# led_1_Arduino.net
KiCad netlist of a schematic drawn in EAGLE
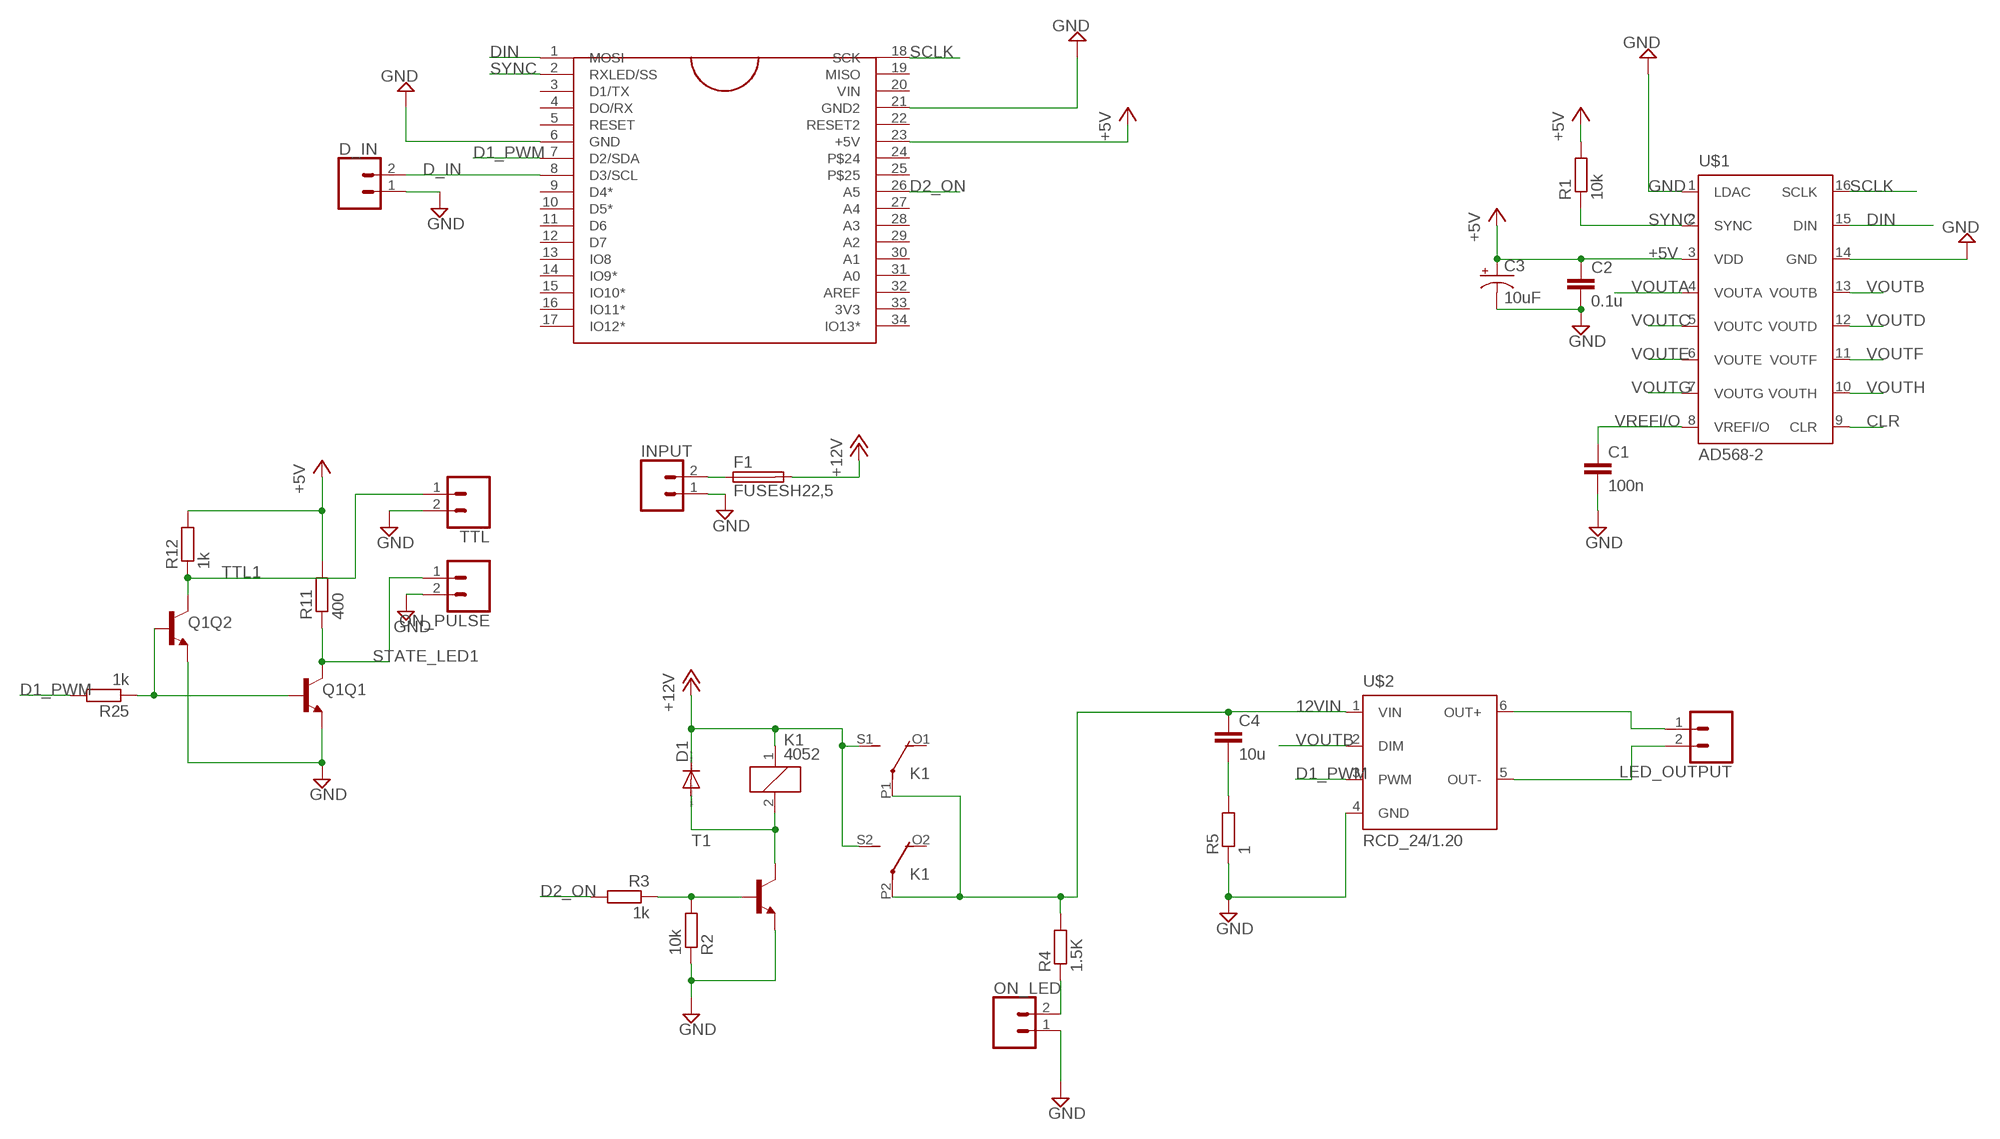
[diagram p0: schematic, sheet 1]

(export (version "E")
  (design (tool "Eeschema 10.0.6"))
  (components
    (comp (ref "C1")
      (value "100n")
      (footprint "eagle-import:C1206")
      (libsource (lib "eagle-import") (part "C-EUC1206"))
    )
    (comp (ref "C2")
      (value "0.1u")
      (footprint "eagle-import:C1206")
      (libsource (lib "eagle-import") (part "C-EUC1206"))
    )
    (comp (ref "C3")
      (value "10uF")
      (footprint "eagle-import:EIA3528")
      (libsource (lib "eagle-import") (part "10UF-POLAR-EIA3528-20V-10%(TANT)"))
    )
    (comp (ref "C4")
      (value "10u")
      (footprint "eagle-import:C1206")
      (libsource (lib "eagle-import") (part "C-EUC1206"))
    )
    (comp (ref "D1")
      (value "DIODE-DO214AC")
      (footprint "eagle-import:DO214AC")
      (libsource (lib "eagle-import") (part "DIODE-DO214AC"))
    )
    (comp (ref "D_IN")
      (value "CONN_02")
      (footprint "eagle-import:1X02")
      (libsource (lib "eagle-import") (part "CONN_02"))
    )
    (comp (ref "F1")
      (value "FUSESH22,5")
      (footprint "eagle-import:SH22,5")
      (libsource (lib "eagle-import") (part "FUSESH22,5"))
    )
    (comp (ref "INPUT")
      (value "CONN_023.5MM")
      (footprint "eagle-import:SCREWTERMINAL-3.5MM-2")
      (libsource (lib "eagle-import") (part "CONN_023.5MM"))
    )
    (comp (ref "K1")
      (value "4052")
      (footprint "eagle-import:F4052")
      (libsource (lib "eagle-import") (part "4052"))
    )
    (comp (ref "LED_OUTPUT")
      (value "CONN_023.5MM")
      (footprint "eagle-import:SCREWTERMINAL-3.5MM-2")
      (libsource (lib "eagle-import") (part "CONN_023.5MM"))
    )
    (comp (ref "ON_LED")
      (value "CONN_02")
      (footprint "eagle-import:1X02")
      (libsource (lib "eagle-import") (part "CONN_02"))
    )
    (comp (ref "ON_PULSE")
      (value "CONN_02")
      (footprint "eagle-import:1X02")
      (libsource (lib "eagle-import") (part "CONN_02"))
    )
    (comp (ref "Q1")
      (value "TRANS_NPN_DUAL_NSM4002-MBT3904DW1T1")
      (footprint "eagle-import:SC70-6")
      (libsource (lib "eagle-import") (part "TRANS_NPN_DUAL_NSM4002-MBT3904DW1T1"))
    )
    (comp (ref "R1")
      (value "10k")
      (footprint "eagle-import:R1206")
      (libsource (lib "eagle-import") (part "R-EU_R1206"))
    )
    (comp (ref "R2")
      (value "10k")
      (footprint "eagle-import:R1206")
      (libsource (lib "eagle-import") (part "R-EU_R1206"))
    )
    (comp (ref "R3")
      (value "1k")
      (footprint "eagle-import:R0805")
      (libsource (lib "eagle-import") (part "R-EU_R0805"))
    )
    (comp (ref "R4")
      (value "1.5K")
      (footprint "eagle-import:R0805")
      (libsource (lib "eagle-import") (part "R-EU_R0805"))
    )
    (comp (ref "R5")
      (value "1")
      (footprint "eagle-import:R1206")
      (libsource (lib "eagle-import") (part "R-EU_R1206"))
    )
    (comp (ref "R11")
      (value "400")
      (footprint "eagle-import:R0805")
      (libsource (lib "eagle-import") (part "R-EU_R0805"))
    )
    (comp (ref "R12")
      (value "1k")
      (footprint "eagle-import:R0805")
      (libsource (lib "eagle-import") (part "R-EU_R0805"))
    )
    (comp (ref "R25")
      (value "1k")
      (footprint "eagle-import:R0805")
      (libsource (lib "eagle-import") (part "R-EU_R0805"))
    )
    (comp (ref "T1")
      (value "-NPN-SOT223")
      (footprint "eagle-import:SOT223")
      (libsource (lib "eagle-import") (part "-NPN-SOT223"))
    )
    (comp (ref "TTL")
      (value "CONN_02")
      (footprint "eagle-import:1X02")
      (libsource (lib "eagle-import") (part "CONN_02"))
    )
    (comp (ref "U$1")
      (value "AD568-2")
      (footprint "eagle-import:TSSOP-16")
      (libsource (lib "eagle-import") (part "AD568-2"))
    )
    (comp (ref "U$2")
      (value "RCD_24/1.20")
      (footprint "eagle-import:RCD-24_W_X3")
      (libsource (lib "eagle-import") (part "RCD_24/1.20"))
    )
    (comp (ref "U$3")
      (value "ARDUINO_MICRO")
      (footprint "eagle-import:ARDUINO_MICRO_PADS")
      (fields (field (name "SPICEPREFIX") "X"))
      (libsource (lib "eagle-import") (part "ARDUINO_MICRO"))
    )
  )
  (nets
    (net (code "1") (name "+5V") (class "Default")
      (node (ref "C2") (pin "1") (pinfunction "1_1") (pintype "passive"))
      (node (ref "C3") (pin "A") (pinfunction "+_A") (pintype "passive"))
      (node (ref "R1") (pin "2") (pinfunction "2_2") (pintype "passive"))
      (node (ref "R11") (pin "2") (pinfunction "2_2") (pintype "passive"))
      (node (ref "R12") (pin "2") (pinfunction "2_2") (pintype "passive"))
      (node (ref "U$1") (pin "3") (pinfunction "VDD_3") (pintype "power_in"))
      (node (ref "U$3") (pin "23") (pinfunction "+5V_23") (pintype "bidirectional"))
    )
    (net (code "2") (name "+12V") (class "Default")
      (node (ref "D1") (pin "C") (pinfunction "C_C") (pintype "passive"))
      (node (ref "F1") (pin "2") (pinfunction "2_2") (pintype "passive"))
      (node (ref "K1") (pin "1") (pinfunction "1_1") (pintype "passive"))
      (node (ref "K1") (pin "S1") (pinfunction "S_S1") (pintype "passive"))
      (node (ref "K1") (pin "S2") (pinfunction "S_S2") (pintype "passive"))
    )
    (net (code "3") (name "/12VIN") (class "Default")
      (node (ref "C4") (pin "1") (pinfunction "1_1") (pintype "passive"))
      (node (ref "K1") (pin "P1") (pinfunction "P_P1") (pintype "passive"))
      (node (ref "K1") (pin "P2") (pinfunction "P_P2") (pintype "passive"))
      (node (ref "R4") (pin "2") (pinfunction "2_2") (pintype "passive"))
      (node (ref "U$2") (pin "1") (pinfunction "VIN_1") (pintype "input"))
    )
    (net (code "4") (name "/CLR") (class "Default")
      (node (ref "U$1") (pin "9") (pinfunction "CLR_9") (pintype "output"))
    )
    (net (code "5") (name "/D1_PWM") (class "Default")
      (node (ref "R25") (pin "2") (pinfunction "2_2") (pintype "passive"))
      (node (ref "U$2") (pin "3") (pinfunction "PWM_3") (pintype "passive"))
      (node (ref "U$3") (pin "7") (pinfunction "D2/SDA_7") (pintype "bidirectional"))
    )
    (net (code "6") (name "/D2_ON") (class "Default")
      (node (ref "R3") (pin "2") (pinfunction "2_2") (pintype "passive"))
      (node (ref "U$3") (pin "26") (pinfunction "A5_26") (pintype "bidirectional"))
    )
    (net (code "7") (name "/DIN") (class "Default")
      (node (ref "U$1") (pin "15") (pinfunction "DIN_15") (pintype "input"))
      (node (ref "U$3") (pin "1") (pinfunction "MOSI_1") (pintype "bidirectional"))
    )
    (net (code "8") (name "/D_IN") (class "Default")
      (node (ref "D_IN") (pin "2") (pinfunction "2_2") (pintype "passive"))
      (node (ref "U$3") (pin "8") (pinfunction "D3/SCL_8") (pintype "bidirectional"))
    )
    (net (code "9") (name "/SCLK") (class "Default")
      (node (ref "U$1") (pin "16") (pinfunction "SCLK_16") (pintype "input"))
      (node (ref "U$3") (pin "18") (pinfunction "SCK_18") (pintype "bidirectional"))
    )
    (net (code "10") (name "/STATE_LED1") (class "Default")
      (node (ref "ON_PULSE") (pin "1") (pinfunction "1_1") (pintype "passive"))
      (node (ref "Q1") (pin "3") (pinfunction "C_3") (pintype "passive"))
      (node (ref "R11") (pin "1") (pinfunction "1_1") (pintype "passive"))
    )
    (net (code "11") (name "/SYNC") (class "Default")
      (node (ref "R1") (pin "1") (pinfunction "1_1") (pintype "passive"))
      (node (ref "U$1") (pin "2") (pinfunction "SYNC_2") (pintype "input"))
      (node (ref "U$3") (pin "2") (pinfunction "RXLED/SS_2") (pintype "bidirectional"))
    )
    (net (code "12") (name "/TTL1") (class "Default")
      (node (ref "Q1") (pin "6") (pinfunction "C_6") (pintype "passive"))
      (node (ref "R12") (pin "1") (pinfunction "1_1") (pintype "passive"))
      (node (ref "TTL") (pin "1") (pinfunction "1_1") (pintype "passive"))
    )
    (net (code "13") (name "/VOUTA") (class "Default")
      (node (ref "U$1") (pin "4") (pinfunction "VOUTA_4") (pintype "output"))
    )
    (net (code "14") (name "/VOUTB") (class "Default")
      (node (ref "U$1") (pin "13") (pinfunction "VOUTB_13") (pintype "output"))
      (node (ref "U$2") (pin "2") (pinfunction "DIM_2") (pintype "passive"))
    )
    (net (code "15") (name "/VOUTC") (class "Default")
      (node (ref "U$1") (pin "5") (pinfunction "VOUTC_5") (pintype "output"))
    )
    (net (code "16") (name "/VOUTD") (class "Default")
      (node (ref "U$1") (pin "12") (pinfunction "VOUTD_12") (pintype "output"))
    )
    (net (code "17") (name "/VOUTE") (class "Default")
      (node (ref "U$1") (pin "6") (pinfunction "VOUTE_6") (pintype "output"))
    )
    (net (code "18") (name "/VOUTF") (class "Default")
      (node (ref "U$1") (pin "11") (pinfunction "VOUTF_11") (pintype "output"))
    )
    (net (code "19") (name "/VOUTG") (class "Default")
      (node (ref "U$1") (pin "7") (pinfunction "VOUTG_7") (pintype "output"))
    )
    (net (code "20") (name "/VOUTH") (class "Default")
      (node (ref "U$1") (pin "10") (pinfunction "VOUTH_10") (pintype "output"))
    )
    (net (code "21") (name "/VREFI{slash}O") (class "Default")
      (node (ref "C1") (pin "1") (pinfunction "1_1") (pintype "passive"))
      (node (ref "U$1") (pin "8") (pinfunction "VREFI/O_8") (pintype "output"))
    )
    (net (code "22") (name "GND") (class "Default")
      (node (ref "C1") (pin "2") (pinfunction "2_2") (pintype "passive"))
      (node (ref "C2") (pin "2") (pinfunction "2_2") (pintype "passive"))
      (node (ref "C3") (pin "C") (pinfunction "-_C") (pintype "passive"))
      (node (ref "D_IN") (pin "1") (pinfunction "1_1") (pintype "passive"))
      (node (ref "INPUT") (pin "1") (pinfunction "1_1") (pintype "passive"))
      (node (ref "ON_LED") (pin "1") (pinfunction "1_1") (pintype "passive"))
      (node (ref "ON_PULSE") (pin "2") (pinfunction "2_2") (pintype "passive"))
      (node (ref "Q1") (pin "1") (pinfunction "E_1") (pintype "passive"))
      (node (ref "Q1") (pin "4") (pinfunction "E_4") (pintype "passive"))
      (node (ref "R2") (pin "1") (pinfunction "1_1") (pintype "passive"))
      (node (ref "R5") (pin "1") (pinfunction "1_1") (pintype "passive"))
      (node (ref "T1") (pin "3") (pinfunction "E_3") (pintype "passive"))
      (node (ref "TTL") (pin "2") (pinfunction "2_2") (pintype "passive"))
      (node (ref "U$1") (pin "1") (pinfunction "LDAC_1") (pintype "bidirectional"))
      (node (ref "U$1") (pin "14") (pinfunction "GND_14") (pintype "power_in"))
      (node (ref "U$2") (pin "4") (pinfunction "GND_4") (pintype "power_in"))
      (node (ref "U$3") (pin "21") (pinfunction "GND2_21") (pintype "power_in"))
      (node (ref "U$3") (pin "6") (pinfunction "GND_6") (pintype "power_in"))
    )
    (net (code "23") (name "Net-(C4-Pad2)") (class "Default")
      (node (ref "C4") (pin "2") (pinfunction "2_2") (pintype "passive"))
      (node (ref "R5") (pin "2") (pinfunction "2_2") (pintype "passive"))
    )
    (net (code "24") (name "Net-(F1-Pad1)") (class "Default")
      (node (ref "F1") (pin "1") (pinfunction "1_1") (pintype "passive"))
      (node (ref "INPUT") (pin "2") (pinfunction "2_2") (pintype "passive"))
    )
    (net (code "25") (name "Net-(ON_LED-Pad2)") (class "Default")
      (node (ref "ON_LED") (pin "2") (pinfunction "2_2") (pintype "passive"))
      (node (ref "R4") (pin "1") (pinfunction "1_1") (pintype "passive"))
    )
    (net (code "26") (name "Net-(Q1A-B)") (class "Default")
      (node (ref "Q1") (pin "2") (pinfunction "B_2") (pintype "passive"))
      (node (ref "Q1") (pin "5") (pinfunction "B_5") (pintype "passive"))
      (node (ref "R25") (pin "1") (pinfunction "1_1") (pintype "passive"))
    )
    (net (code "27") (name "Net-(T1-B)") (class "Default")
      (node (ref "R2") (pin "2") (pinfunction "2_2") (pintype "passive"))
      (node (ref "R3") (pin "1") (pinfunction "1_1") (pintype "passive"))
      (node (ref "T1") (pin "1") (pinfunction "B_1") (pintype "passive"))
    )
    (net (code "28") (name "Net-(T1-C)") (class "Default")
      (node (ref "D1") (pin "A") (pinfunction "A_A") (pintype "passive"))
      (node (ref "K1") (pin "2") (pinfunction "2_2") (pintype "passive"))
      (node (ref "T1") (pin "4") (pinfunction "C_4") (pintype "passive"))
    )
    (net (code "29") (name "Net-(U$2-OUT+)") (class "Default")
      (node (ref "LED_OUTPUT") (pin "1") (pinfunction "1_1") (pintype "passive"))
      (node (ref "U$2") (pin "6") (pinfunction "OUT+_6") (pintype "output"))
    )
    (net (code "30") (name "Net-(U$2-OUT-)") (class "Default")
      (node (ref "LED_OUTPUT") (pin "2") (pinfunction "2_2") (pintype "passive"))
      (node (ref "U$2") (pin "5") (pinfunction "OUT-_5") (pintype "output"))
    )
    (net (code "31") (name "unconnected-(K1B-O-PadO1)") (class "Default")
      (node (ref "K1") (pin "O1") (pinfunction "O_O1") (pintype "passive"))
    )
    (net (code "32") (name "unconnected-(K1C-O-PadO2)") (class "Default")
      (node (ref "K1") (pin "O2") (pinfunction "O_O2") (pintype "passive"))
    )
    (net (code "33") (name "unconnected-(U$3-3V3-Pad33)") (class "Default")
      (node (ref "U$3") (pin "33") (pinfunction "3V3_33") (pintype "bidirectional"))
    )
    (net (code "34") (name "unconnected-(U$3-A0-Pad31)") (class "Default")
      (node (ref "U$3") (pin "31") (pinfunction "A0_31") (pintype "bidirectional"))
    )
    (net (code "35") (name "unconnected-(U$3-A1-Pad30)") (class "Default")
      (node (ref "U$3") (pin "30") (pinfunction "A1_30") (pintype "bidirectional"))
    )
    (net (code "36") (name "unconnected-(U$3-A2-Pad29)") (class "Default")
      (node (ref "U$3") (pin "29") (pinfunction "A2_29") (pintype "bidirectional"))
    )
    (net (code "37") (name "unconnected-(U$3-A3-Pad28)") (class "Default")
      (node (ref "U$3") (pin "28") (pinfunction "A3_28") (pintype "bidirectional"))
    )
    (net (code "38") (name "unconnected-(U$3-A4-Pad27)") (class "Default")
      (node (ref "U$3") (pin "27") (pinfunction "A4_27") (pintype "bidirectional"))
    )
    (net (code "39") (name "unconnected-(U$3-AREF-Pad32)") (class "Default")
      (node (ref "U$3") (pin "32") (pinfunction "AREF_32") (pintype "bidirectional"))
    )
    (net (code "40") (name "unconnected-(U$3-D1{slash}TX-Pad3)") (class "Default")
      (node (ref "U$3") (pin "3") (pinfunction "D1/TX_3") (pintype "bidirectional"))
    )
    (net (code "41") (name "unconnected-(U$3-D4*-Pad9)") (class "Default")
      (node (ref "U$3") (pin "9") (pinfunction "D4*_9") (pintype "bidirectional"))
    )
    (net (code "42") (name "unconnected-(U$3-D5*-Pad10)") (class "Default")
      (node (ref "U$3") (pin "10") (pinfunction "D5*_10") (pintype "bidirectional"))
    )
    (net (code "43") (name "unconnected-(U$3-D6-Pad11)") (class "Default")
      (node (ref "U$3") (pin "11") (pinfunction "D6_11") (pintype "bidirectional"))
    )
    (net (code "44") (name "unconnected-(U$3-D7-Pad12)") (class "Default")
      (node (ref "U$3") (pin "12") (pinfunction "D7_12") (pintype "bidirectional"))
    )
    (net (code "45") (name "unconnected-(U$3-DO{slash}RX-Pad4)") (class "Default")
      (node (ref "U$3") (pin "4") (pinfunction "DO/RX_4") (pintype "bidirectional"))
    )
    (net (code "46") (name "unconnected-(U$3-IO8-Pad13)") (class "Default")
      (node (ref "U$3") (pin "13") (pinfunction "IO8_13") (pintype "bidirectional"))
    )
    (net (code "47") (name "unconnected-(U$3-IO9*-Pad14)") (class "Default")
      (node (ref "U$3") (pin "14") (pinfunction "IO9*_14") (pintype "bidirectional"))
    )
    (net (code "48") (name "unconnected-(U$3-IO10*-Pad15)") (class "Default")
      (node (ref "U$3") (pin "15") (pinfunction "IO10*_15") (pintype "bidirectional"))
    )
    (net (code "49") (name "unconnected-(U$3-IO11*-Pad16)") (class "Default")
      (node (ref "U$3") (pin "16") (pinfunction "IO11*_16") (pintype "bidirectional"))
    )
    (net (code "50") (name "unconnected-(U$3-IO12*-Pad17)") (class "Default")
      (node (ref "U$3") (pin "17") (pinfunction "IO12*_17") (pintype "bidirectional"))
    )
    (net (code "51") (name "unconnected-(U$3-IO13*-Pad34)") (class "Default")
      (node (ref "U$3") (pin "34") (pinfunction "IO13*_34") (pintype "bidirectional"))
    )
    (net (code "52") (name "unconnected-(U$3-MISO-Pad19)") (class "Default")
      (node (ref "U$3") (pin "19") (pinfunction "MISO_19") (pintype "bidirectional"))
    )
    (net (code "53") (name "unconnected-(U$3-P$24-Pad24)") (class "Default")
      (node (ref "U$3") (pin "24") (pinfunction "P$24_24") (pintype "bidirectional"))
    )
    (net (code "54") (name "unconnected-(U$3-P$25-Pad25)") (class "Default")
      (node (ref "U$3") (pin "25") (pinfunction "P$25_25") (pintype "bidirectional"))
    )
    (net (code "55") (name "unconnected-(U$3-RESET-Pad5)") (class "Default")
      (node (ref "U$3") (pin "5") (pinfunction "RESET_5") (pintype "bidirectional"))
    )
    (net (code "56") (name "unconnected-(U$3-RESET2-Pad22)") (class "Default")
      (node (ref "U$3") (pin "22") (pinfunction "RESET2_22") (pintype "bidirectional"))
    )
    (net (code "57") (name "unconnected-(U$3-VIN-Pad20)") (class "Default")
      (node (ref "U$3") (pin "20") (pinfunction "VIN_20") (pintype "bidirectional"))
    )
  )
)
